# ECG_ACCEL_Board.net
KiCad netlist of a schematic drawn in Altium Designer
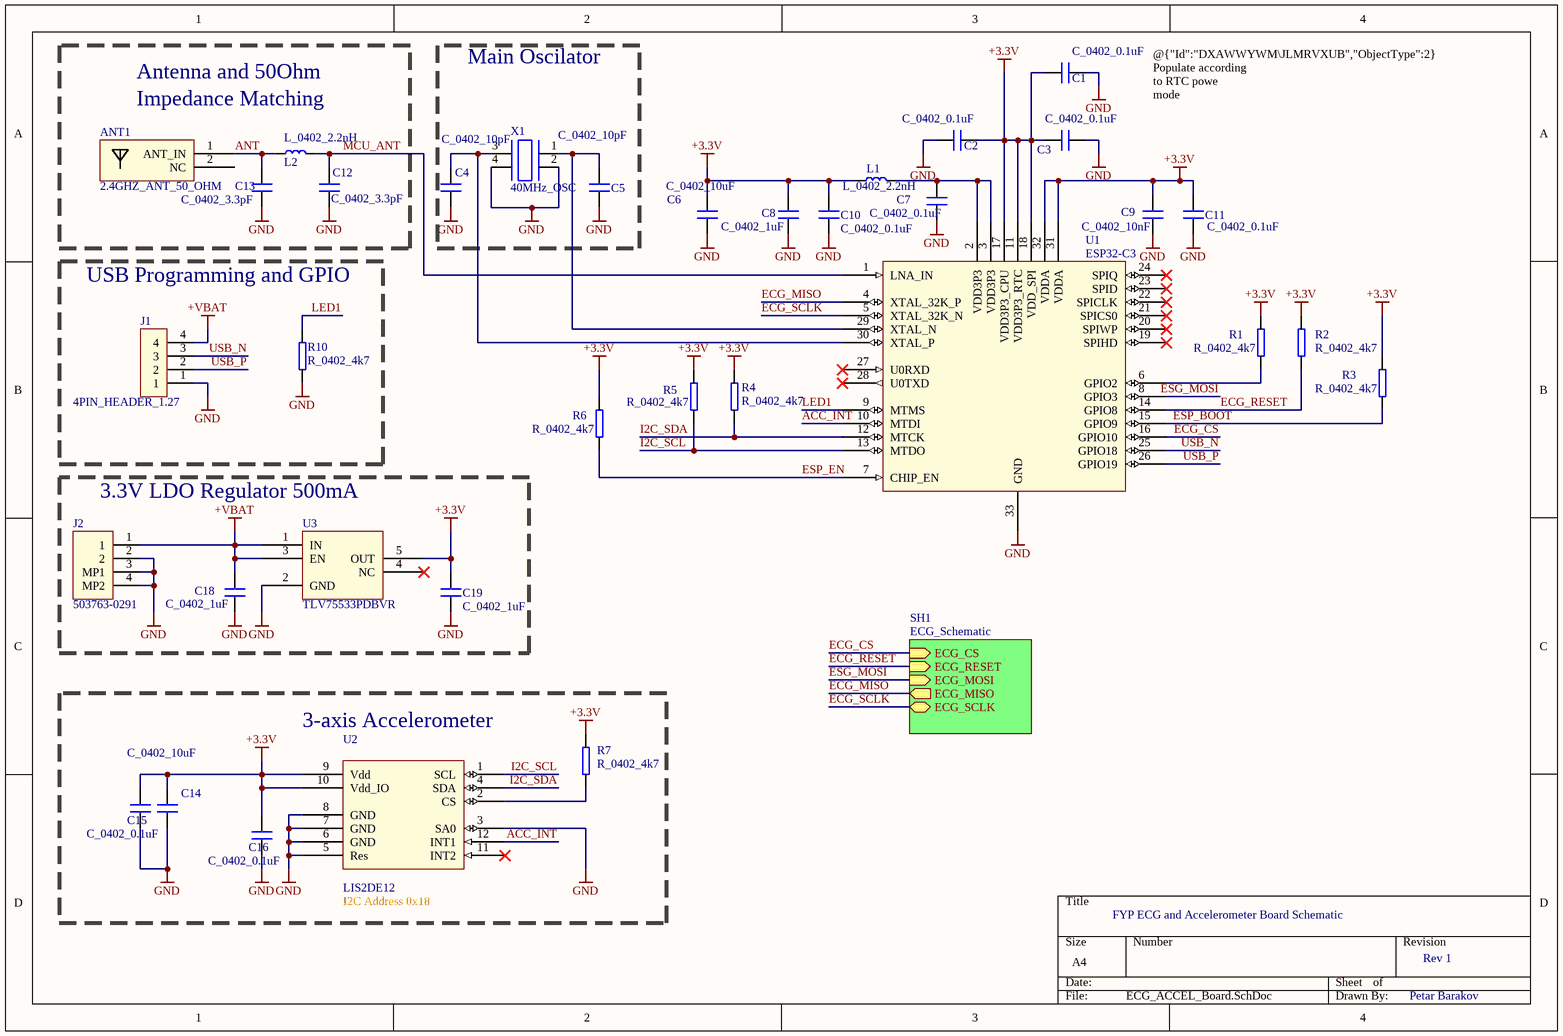
[diagram p0: ECG_ACCEL_Board.SchDoc]

(export (version "E")
  (design (tool "Eeschema 10.0.6"))
  (components
    (comp (ref "ANT1")
      (value "2.4GHZ_ANT_50_OHM")
      (footprint "Chip2PinSM127P600-8N")
      (description "2.4GHz Chip Antenna 50 Ohm Impedance ANT2012LL00R2400A")
      (libsource (lib "Petar B") (part "2.4GHZ_ANT_50_OHM"))
    )
    (comp (ref "C1")
      (value "C_0402_0.1uF")
      (footprint "C_0402")
      (fields (field (name "JLC PART NUMBER") "C1525"))
      (libsource (lib "Petar B") (part "Cap_symbol"))
    )
    (comp (ref "C2")
      (value "C_0402_0.1uF")
      (footprint "C_0402")
      (fields (field (name "JLC PART NUMBER") "C1525"))
      (libsource (lib "Petar B") (part "Cap_symbol"))
    )
    (comp (ref "C3")
      (value "C_0402_0.1uF")
      (footprint "C_0402")
      (fields (field (name "JLC PART NUMBER") "C1525"))
      (libsource (lib "Petar B") (part "Cap_symbol"))
    )
    (comp (ref "C4")
      (value "C_0402_10pF")
      (footprint "C_0402")
      (fields (field (name "JLC PART NUMBER") "C32949"))
      (libsource (lib "Petar B") (part "Cap_symbol"))
    )
    (comp (ref "C5")
      (value "C_0402_10pF")
      (footprint "C_0402")
      (fields (field (name "JLC PART NUMBER") "C32949"))
      (libsource (lib "Petar B") (part "Cap_symbol"))
    )
    (comp (ref "C6")
      (value "C_0402_10uF")
      (footprint "C_0402")
      (fields (field (name "JLC PART NUMBER") "C15525"))
      (libsource (lib "Petar B") (part "Cap_symbol"))
    )
    (comp (ref "C7")
      (value "C_0402_0.1uF")
      (footprint "C_0402")
      (fields (field (name "JLC PART NUMBER") "C1525"))
      (libsource (lib "Petar B") (part "Cap_symbol"))
    )
    (comp (ref "C8")
      (value "C_0402_1uF")
      (footprint "C_0402")
      (fields (field (name "JLC PART NUMBER") "C52923"))
      (libsource (lib "Petar B") (part "Cap_symbol"))
    )
    (comp (ref "C9")
      (value "C_0402_10nF")
      (footprint "C_0402")
      (fields (field (name "JLC PART NUMBER") "C15195"))
      (libsource (lib "Petar B") (part "Cap_symbol"))
    )
    (comp (ref "C10")
      (value "C_0402_0.1uF")
      (footprint "C_0402")
      (fields (field (name "JLC PART NUMBER") "C1525"))
      (libsource (lib "Petar B") (part "Cap_symbol"))
    )
    (comp (ref "C11")
      (value "C_0402_0.1uF")
      (footprint "C_0402")
      (fields (field (name "JLC PART NUMBER") "C1525"))
      (libsource (lib "Petar B") (part "Cap_symbol"))
    )
    (comp (ref "C12")
      (value "C_0402_3.3pF")
      (footprint "C_0402")
      (fields (field (name "JLC PART NUMBER") "C326841"))
      (libsource (lib "Petar B") (part "Cap_symbol"))
    )
    (comp (ref "C13")
      (value "C_0402_3.3pF")
      (footprint "C_0402")
      (fields (field (name "JLC PART NUMBER") "C326841"))
      (libsource (lib "Petar B") (part "Cap_symbol"))
    )
    (comp (ref "C14")
      (value "C_0402_10uF")
      (footprint "C_0402")
      (fields (field (name "JLC PART NUMBER") "C15525"))
      (libsource (lib "Petar B") (part "Cap_symbol"))
    )
    (comp (ref "C15")
      (value "C_0402_0.1uF")
      (footprint "C_0402")
      (fields (field (name "JLC PART NUMBER") "C1525"))
      (libsource (lib "Petar B") (part "Cap_symbol"))
    )
    (comp (ref "C16")
      (value "C_0402_0.1uF")
      (footprint "C_0402")
      (fields (field (name "JLC PART NUMBER") "C1525"))
      (libsource (lib "Petar B") (part "Cap_symbol"))
    )
    (comp (ref "C18")
      (value "C_0402_1uF")
      (footprint "C_0402")
      (fields (field (name "JLC PART NUMBER") "C52923"))
      (libsource (lib "Petar B") (part "Cap_symbol"))
    )
    (comp (ref "C19")
      (value "C_0402_1uF")
      (footprint "C_0402")
      (fields (field (name "JLC PART NUMBER") "C52923"))
      (libsource (lib "Petar B") (part "Cap_symbol"))
    )
    (comp (ref "J1")
      (value "4PIN_HEADER_1.27")
      (footprint "4PIN_HEADER_1.27-Footprint-1")
      (libsource (lib "Petar B") (part "4PIN_HEADER_1.27-Symbol-1"))
    )
    (comp (ref "J2")
      (value "503763-0291")
      (footprint "Molex 503763-0291")
      (description "Molex 503763-0291")
      (libsource (lib "Petar B") (part "503763-0291"))
    )
    (comp (ref "L1")
      (value "L_0402_2.2nH")
      (footprint "L_0402")
      (fields (field (name "JLC PART NUMBER") "C92035"))
      (libsource (lib "Petar B") (part "Ind_Symbol"))
    )
    (comp (ref "L2")
      (value "L_0402_2.2nH")
      (footprint "L_0402")
      (fields (field (name "JLC PART NUMBER") "C92035"))
      (libsource (lib "Petar B") (part "Ind_Symbol"))
    )
    (comp (ref "R1")
      (value "R_0402_4k7")
      (footprint "R_0402")
      (fields (field (name "JLC PART NUMBER") "C25900"))
      (libsource (lib "Petar B") (part "R_symbol"))
    )
    (comp (ref "R2")
      (value "R_0402_4k7")
      (footprint "R_0402")
      (fields (field (name "JLC PART NUMBER") "C25900"))
      (libsource (lib "Petar B") (part "R_symbol"))
    )
    (comp (ref "R3")
      (value "R_0402_4k7")
      (footprint "R_0402")
      (fields (field (name "JLC PART NUMBER") "C25900"))
      (libsource (lib "Petar B") (part "R_symbol"))
    )
    (comp (ref "R4")
      (value "R_0402_4k7")
      (footprint "R_0402")
      (fields (field (name "JLC PART NUMBER") "C25900"))
      (libsource (lib "Petar B") (part "R_symbol"))
    )
    (comp (ref "R5")
      (value "R_0402_4k7")
      (footprint "R_0402")
      (fields (field (name "JLC PART NUMBER") "C25900"))
      (libsource (lib "Petar B") (part "R_symbol"))
    )
    (comp (ref "R6")
      (value "R_0402_4k7")
      (footprint "R_0402")
      (fields (field (name "JLC PART NUMBER") "C25900"))
      (libsource (lib "Petar B") (part "R_symbol"))
    )
    (comp (ref "R7")
      (value "R_0402_4k7")
      (footprint "R_0402")
      (fields (field (name "JLC PART NUMBER") "C25900"))
      (libsource (lib "Petar B") (part "R_symbol"))
    )
    (comp (ref "R10")
      (value "R_0402_4k7")
      (footprint "R_0402")
      (fields (field (name "JLC PART NUMBER") "C25900"))
      (libsource (lib "Petar B") (part "R_symbol"))
    )
    (comp (ref "U1")
      (value "ESP32-C3")
      (footprint "QFN127P600-8N")
      (description "33 pin ESP32_C3 Microcontroller")
      (fields (field (name "JLC PART NUMBER") "C2858491"))
      (libsource (lib "Petar B") (part "ESP32-C3_symbol"))
    )
    (comp (ref "U2")
      (value "LIS2DE12")
      (footprint "LIS2DE12-Footprint-1")
      (description "Accelerometers MEMS digital output motion sensor: ultra-low-power high-performance 3-axis \"femt")
      (fields (field (name "JLC PART NUMBER") "C155639"))
      (libsource (lib "Petar B") (part "LIS2DE12"))
    )
    (comp (ref "U3")
      (value "TLV75533PDBVR")
      (footprint "SOT95P280X145-5N")
      (fields (field (name "JLC PART NUMBER") "C404027"))
      (libsource (lib "Petar B") (part "TLV75533PDBVR-Symbol"))
    )
    (comp (ref "X1")
      (value "40MHz_OSC")
      (footprint "40MHz_OSC-Footprint-1")
      (description "40 MHZ Oscillator, 10pF load capacitance")
      (fields (field (name "JLC PART NUMBER") "C426988"))
      (libsource (lib "Petar B") (part "OSC_SYMB"))
    )
  )
  (nets
    (net (code "1") (name "+3.3V") (class "Default")
      (node (ref "C1") (pin "1") (pinfunction "1_1") (pintype "passive"))
      (node (ref "C10") (pin "1") (pinfunction "1_1") (pintype "passive"))
      (node (ref "C11") (pin "2") (pinfunction "2_2") (pintype "passive"))
      (node (ref "C14") (pin "2") (pinfunction "2_2") (pintype "passive"))
      (node (ref "C15") (pin "2") (pinfunction "2_2") (pintype "passive"))
      (node (ref "C16") (pin "2") (pinfunction "2_2") (pintype "passive"))
      (node (ref "C19") (pin "2") (pinfunction "2_2") (pintype "passive"))
      (node (ref "C2") (pin "2") (pinfunction "2_2") (pintype "passive"))
      (node (ref "C3") (pin "1") (pinfunction "1_1") (pintype "passive"))
      (node (ref "C6") (pin "2") (pinfunction "2_2") (pintype "passive"))
      (node (ref "C8") (pin "2") (pinfunction "2_2") (pintype "passive"))
      (node (ref "C9") (pin "2") (pinfunction "2_2") (pintype "passive"))
      (node (ref "L1") (pin "1") (pinfunction "1_1") (pintype "passive"))
      (node (ref "R1") (pin "1") (pinfunction "1_1") (pintype "passive"))
      (node (ref "R2") (pin "1") (pinfunction "1_1") (pintype "passive"))
      (node (ref "R3") (pin "1") (pinfunction "1_1") (pintype "passive"))
      (node (ref "R4") (pin "1") (pinfunction "1_1") (pintype "passive"))
      (node (ref "R5") (pin "1") (pinfunction "1_1") (pintype "passive"))
      (node (ref "R6") (pin "1") (pinfunction "1_1") (pintype "passive"))
      (node (ref "R7") (pin "1") (pinfunction "1_1") (pintype "passive"))
      (node (ref "U1") (pin "11") (pinfunction "VDD3P3_RTC_11") (pintype "power_in"))
      (node (ref "U1") (pin "17") (pinfunction "VDD3P3_CPU_17") (pintype "power_in"))
      (node (ref "U1") (pin "18") (pinfunction "VDD_SPI_18") (pintype "power_in"))
      (node (ref "U1") (pin "31") (pinfunction "VDDA_31") (pintype "power_in"))
      (node (ref "U1") (pin "32") (pinfunction "VDDA_32") (pintype "power_in"))
      (node (ref "U2") (pin "10") (pinfunction "Vdd_IO_10") (pintype "power_in"))
      (node (ref "U2") (pin "9") (pinfunction "Vdd_9") (pintype "power_in"))
      (node (ref "U3") (pin "5") (pinfunction "OUT_5") (pintype "passive"))
    )
    (net (code "2") (name "+VBAT") (class "Default")
      (node (ref "C18") (pin "2") (pinfunction "2_2") (pintype "passive"))
      (node (ref "J1") (pin "4") (pinfunction "4_4") (pintype "passive"))
      (node (ref "J2") (pin "1") (pinfunction "1_1") (pintype "passive"))
      (node (ref "U3") (pin "1") (pinfunction "IN_1") (pintype "passive"))
      (node (ref "U3") (pin "3") (pinfunction "EN_3") (pintype "passive"))
    )
    (net (code "3") (name "/ACC_INT") (class "Default")
      (node (ref "U1") (pin "10") (pinfunction "MTDI_10") (pintype "bidirectional"))
      (node (ref "U2") (pin "12") (pinfunction "INT1_12") (pintype "input"))
    )
    (net (code "4") (name "/ANT") (class "Default")
      (node (ref "ANT1") (pin "1") (pinfunction "ANT_IN_1") (pintype "passive"))
      (node (ref "C13") (pin "2") (pinfunction "2_2") (pintype "passive"))
      (node (ref "L2") (pin "1") (pinfunction "1_1") (pintype "passive"))
    )
    (net (code "5") (name "/ECG_CS") (class "Default")
      (node (ref "U1") (pin "16") (pinfunction "GPIO10_16") (pintype "bidirectional"))
    )
    (net (code "6") (name "/ECG_MISO") (class "Default")
      (node (ref "U1") (pin "4") (pinfunction "XTAL_32K_P_4") (pintype "bidirectional"))
    )
    (net (code "7") (name "/ECG_RESET") (class "Default")
      (node (ref "R2") (pin "2") (pinfunction "2_2") (pintype "passive"))
      (node (ref "U1") (pin "14") (pinfunction "GPIO8_14") (pintype "bidirectional"))
    )
    (net (code "8") (name "/ECG_SCLK") (class "Default")
      (node (ref "U1") (pin "5") (pinfunction "XTAL_32K_N_5") (pintype "bidirectional"))
    )
    (net (code "9") (name "/ESG_MOSI") (class "Default")
      (node (ref "U1") (pin "8") (pinfunction "GPIO3_8") (pintype "bidirectional"))
    )
    (net (code "10") (name "/ESP_BOOT") (class "Default")
      (node (ref "R3") (pin "2") (pinfunction "2_2") (pintype "passive"))
      (node (ref "U1") (pin "15") (pinfunction "GPIO9_15") (pintype "bidirectional"))
    )
    (net (code "11") (name "/ESP_EN") (class "Default")
      (node (ref "R6") (pin "2") (pinfunction "2_2") (pintype "passive"))
      (node (ref "U1") (pin "7") (pinfunction "CHIP_EN_7") (pintype "input"))
    )
    (net (code "12") (name "/I2C_SCL") (class "Default")
      (node (ref "R5") (pin "2") (pinfunction "2_2") (pintype "passive"))
      (node (ref "U1") (pin "13") (pinfunction "MTDO_13") (pintype "bidirectional"))
      (node (ref "U2") (pin "1") (pinfunction "SCL_1") (pintype "bidirectional"))
    )
    (net (code "13") (name "/I2C_SDA") (class "Default")
      (node (ref "R4") (pin "2") (pinfunction "2_2") (pintype "passive"))
      (node (ref "U1") (pin "12") (pinfunction "MTCK_12") (pintype "bidirectional"))
      (node (ref "U2") (pin "4") (pinfunction "SDA_4") (pintype "bidirectional"))
    )
    (net (code "14") (name "/LED1") (class "Default")
      (node (ref "R10") (pin "1") (pinfunction "1_1") (pintype "passive"))
      (node (ref "U1") (pin "9") (pinfunction "MTMS_9") (pintype "bidirectional"))
    )
    (net (code "15") (name "/MCU_ANT") (class "Default")
      (node (ref "C12") (pin "2") (pinfunction "2_2") (pintype "passive"))
      (node (ref "L2") (pin "2") (pinfunction "2_2") (pintype "passive"))
      (node (ref "U1") (pin "1") (pinfunction "LNA_IN_1") (pintype "input"))
    )
    (net (code "16") (name "/USB_N") (class "Default")
      (node (ref "J1") (pin "3") (pinfunction "3_3") (pintype "passive"))
      (node (ref "U1") (pin "25") (pinfunction "GPIO18_25") (pintype "bidirectional"))
    )
    (net (code "17") (name "/USB_P") (class "Default")
      (node (ref "J1") (pin "2") (pinfunction "2_2") (pintype "passive"))
      (node (ref "U1") (pin "26") (pinfunction "GPIO19_26") (pintype "bidirectional"))
    )
    (net (code "18") (name "GND") (class "Default")
      (node (ref "C1") (pin "2") (pinfunction "2_2") (pintype "passive"))
      (node (ref "C10") (pin "2") (pinfunction "2_2") (pintype "passive"))
      (node (ref "C11") (pin "1") (pinfunction "1_1") (pintype "passive"))
      (node (ref "C12") (pin "1") (pinfunction "1_1") (pintype "passive"))
      (node (ref "C13") (pin "1") (pinfunction "1_1") (pintype "passive"))
      (node (ref "C14") (pin "1") (pinfunction "1_1") (pintype "passive"))
      (node (ref "C15") (pin "1") (pinfunction "1_1") (pintype "passive"))
      (node (ref "C16") (pin "1") (pinfunction "1_1") (pintype "passive"))
      (node (ref "C18") (pin "1") (pinfunction "1_1") (pintype "passive"))
      (node (ref "C19") (pin "1") (pinfunction "1_1") (pintype "passive"))
      (node (ref "C2") (pin "1") (pinfunction "1_1") (pintype "passive"))
      (node (ref "C3") (pin "2") (pinfunction "2_2") (pintype "passive"))
      (node (ref "C4") (pin "1") (pinfunction "1_1") (pintype "passive"))
      (node (ref "C5") (pin "1") (pinfunction "1_1") (pintype "passive"))
      (node (ref "C6") (pin "1") (pinfunction "1_1") (pintype "passive"))
      (node (ref "C7") (pin "2") (pinfunction "2_2") (pintype "passive"))
      (node (ref "C8") (pin "1") (pinfunction "1_1") (pintype "passive"))
      (node (ref "C9") (pin "1") (pinfunction "1_1") (pintype "passive"))
      (node (ref "J1") (pin "1") (pinfunction "1_1") (pintype "passive"))
      (node (ref "J2") (pin "2") (pinfunction "2_2") (pintype "passive"))
      (node (ref "J2") (pin "3") (pinfunction "MP1_3") (pintype "passive"))
      (node (ref "J2") (pin "4") (pinfunction "MP2_4") (pintype "passive"))
      (node (ref "R10") (pin "2") (pinfunction "2_2") (pintype "passive"))
      (node (ref "U1") (pin "33") (pinfunction "GND_33") (pintype "power_in"))
      (node (ref "U2") (pin "3") (pinfunction "SA0_3") (pintype "bidirectional"))
      (node (ref "U2") (pin "5") (pinfunction "Res_5") (pintype "power_in"))
      (node (ref "U2") (pin "6") (pinfunction "GND_6") (pintype "power_in"))
      (node (ref "U2") (pin "7") (pinfunction "GND_7") (pintype "power_in"))
      (node (ref "U2") (pin "8") (pinfunction "GND_8") (pintype "power_in"))
      (node (ref "U3") (pin "2") (pinfunction "GND_2") (pintype "passive"))
      (node (ref "X1") (pin "2") (pinfunction "2_2") (pintype "passive"))
      (node (ref "X1") (pin "4") (pinfunction "4_4") (pintype "passive"))
    )
    (net (code "19") (name "Net-(C7-Pad1)") (class "Default")
      (node (ref "C7") (pin "1") (pinfunction "1_1") (pintype "passive"))
      (node (ref "L1") (pin "2") (pinfunction "2_2") (pintype "passive"))
      (node (ref "U1") (pin "2") (pinfunction "VDD3P3_2") (pintype "power_in"))
      (node (ref "U1") (pin "3") (pinfunction "VDD3P3_3") (pintype "power_in"))
    )
    (net (code "20") (name "Net-(U1-GPIO2)") (class "Default")
      (node (ref "R1") (pin "2") (pinfunction "2_2") (pintype "passive"))
      (node (ref "U1") (pin "6") (pinfunction "GPIO2_6") (pintype "bidirectional"))
    )
    (net (code "21") (name "Net-(U1-XTAL_N)") (class "Default")
      (node (ref "C5") (pin "2") (pinfunction "2_2") (pintype "passive"))
      (node (ref "U1") (pin "29") (pinfunction "XTAL_N_29") (pintype "bidirectional"))
      (node (ref "X1") (pin "1") (pinfunction "1_1") (pintype "passive"))
    )
    (net (code "22") (name "Net-(U1-XTAL_P)") (class "Default")
      (node (ref "C4") (pin "2") (pinfunction "2_2") (pintype "passive"))
      (node (ref "U1") (pin "30") (pinfunction "XTAL_P_30") (pintype "bidirectional"))
      (node (ref "X1") (pin "3") (pinfunction "3_3") (pintype "passive"))
    )
    (net (code "23") (name "Net-(U2-CS)") (class "Default")
      (node (ref "R7") (pin "2") (pinfunction "2_2") (pintype "passive"))
      (node (ref "U2") (pin "2") (pinfunction "CS_2") (pintype "bidirectional"))
    )
    (net (code "24") (name "unconnected-(ANT1-NC-Pad2)") (class "Default")
      (node (ref "ANT1") (pin "2") (pinfunction "NC_2") (pintype "passive"))
    )
    (net (code "25") (name "unconnected-(U1-SPICLK-Pad22)") (class "Default")
      (node (ref "U1") (pin "22") (pinfunction "SPICLK_22") (pintype "bidirectional+no_connect"))
    )
    (net (code "26") (name "unconnected-(U1-SPICS0-Pad21)") (class "Default")
      (node (ref "U1") (pin "21") (pinfunction "SPICS0_21") (pintype "bidirectional+no_connect"))
    )
    (net (code "27") (name "unconnected-(U1-SPID-Pad23)") (class "Default")
      (node (ref "U1") (pin "23") (pinfunction "SPID_23") (pintype "bidirectional+no_connect"))
    )
    (net (code "28") (name "unconnected-(U1-SPIHD-Pad19)") (class "Default")
      (node (ref "U1") (pin "19") (pinfunction "SPIHD_19") (pintype "bidirectional+no_connect"))
    )
    (net (code "29") (name "unconnected-(U1-SPIQ-Pad24)") (class "Default")
      (node (ref "U1") (pin "24") (pinfunction "SPIQ_24") (pintype "bidirectional+no_connect"))
    )
    (net (code "30") (name "unconnected-(U1-SPIWP-Pad20)") (class "Default")
      (node (ref "U1") (pin "20") (pinfunction "SPIWP_20") (pintype "bidirectional+no_connect"))
    )
    (net (code "31") (name "unconnected-(U1-U0RXD-Pad27)") (class "Default")
      (node (ref "U1") (pin "27") (pinfunction "U0RXD_27") (pintype "input+no_connect"))
    )
    (net (code "32") (name "unconnected-(U1-U0TXD-Pad28)") (class "Default")
      (node (ref "U1") (pin "28") (pinfunction "U0TXD_28") (pintype "output+no_connect"))
    )
    (net (code "33") (name "unconnected-(U2-INT2-Pad11)") (class "Default")
      (node (ref "U2") (pin "11") (pinfunction "INT2_11") (pintype "input+no_connect"))
    )
    (net (code "34") (name "unconnected-(U3-NC-Pad4)") (class "Default")
      (node (ref "U3") (pin "4") (pinfunction "NC_4") (pintype "passive+no_connect"))
    )
  )
)
